# fhd-gs.net
KiCad netlist of a schematic drawn in Altium Designer
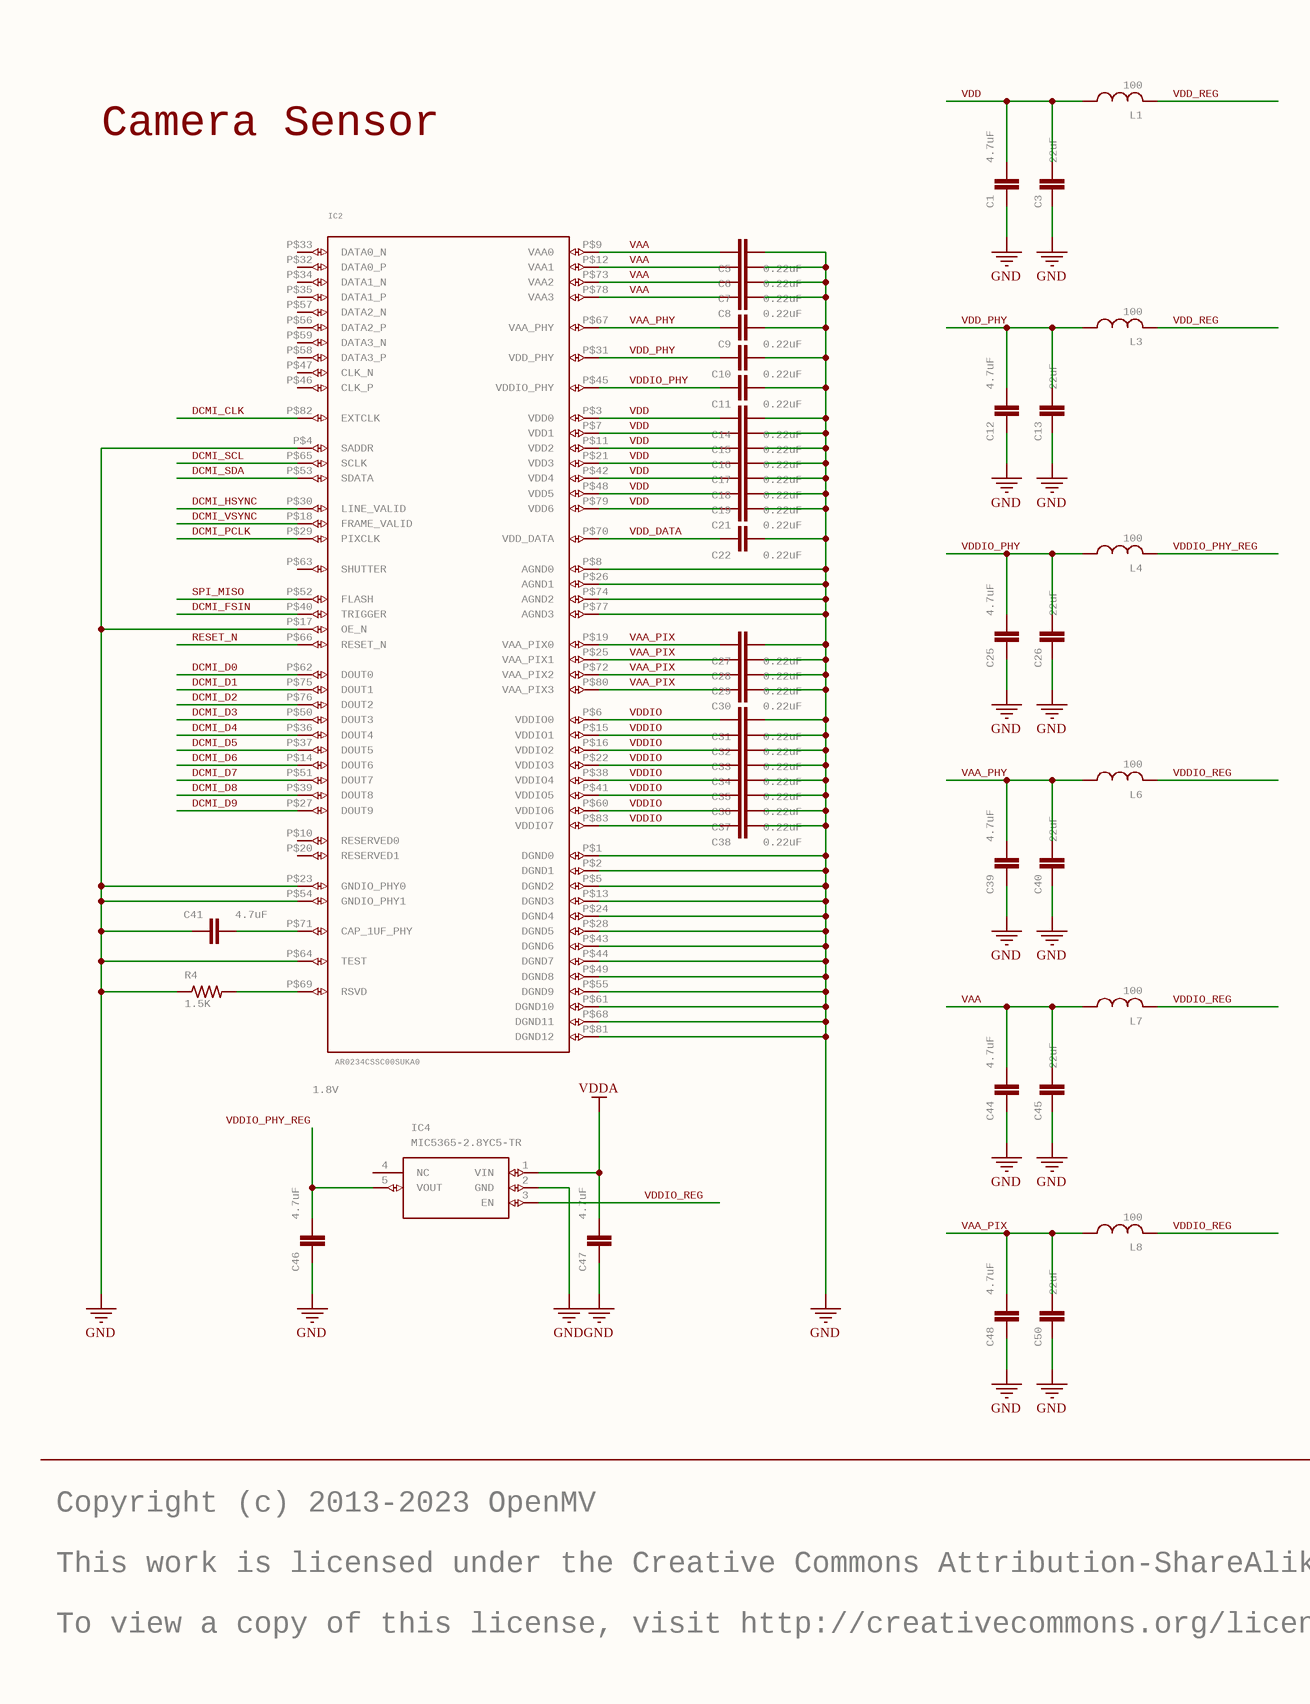
[diagram p0: fhd-gs.SchDoc, left]
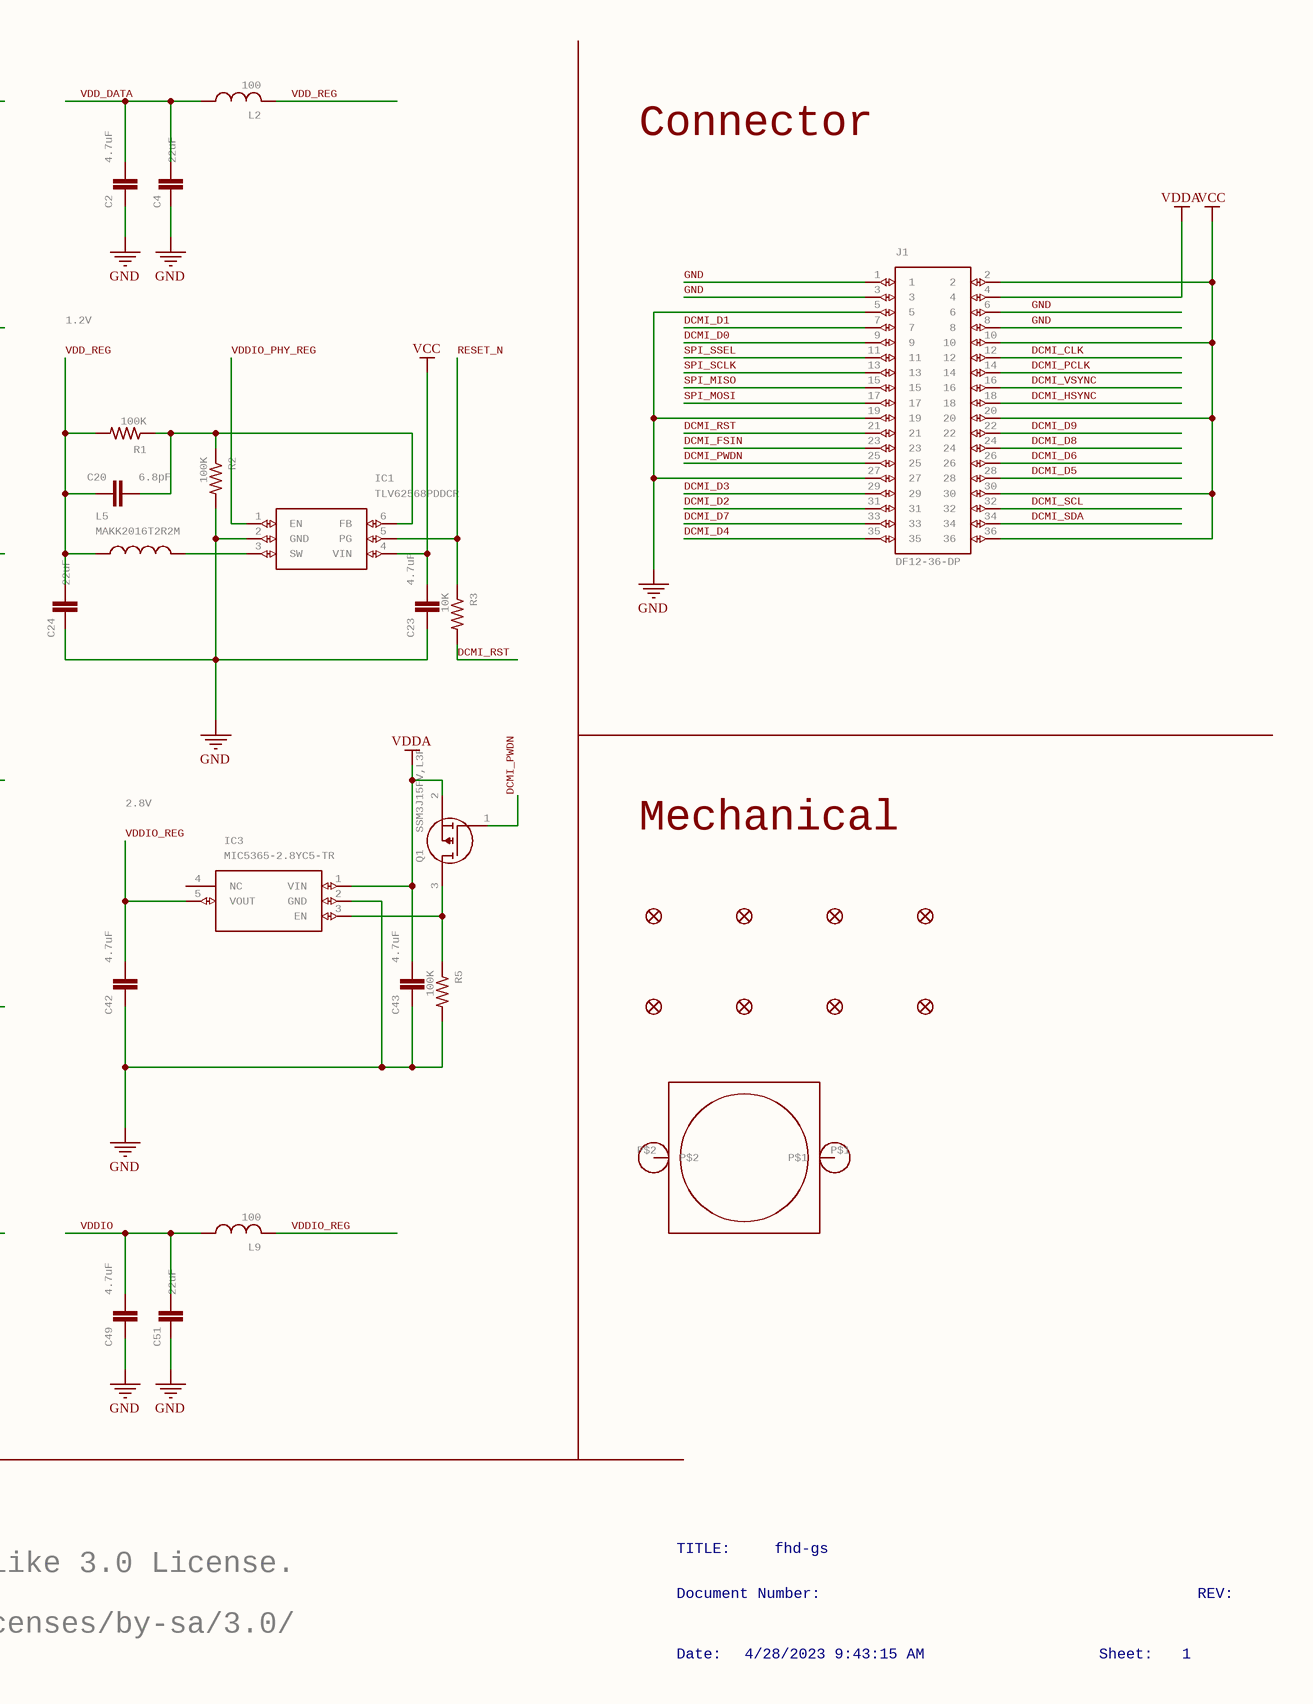
[diagram p1: fhd-gs.SchDoc, right]

(export (version "E")
  (design (tool "Eeschema 10.0.6"))
  (components
    (comp (ref "C1")
      (value "4.7uF")
      (footprint "0402")
      (description "0402 (1005 Metric) Nick Garner - TeleSense")
      (fields (field (name "MPN") "JMK105BBJ475MV-F"))
      (libsource (lib "") (part "CAP_0402_1"))
    )
    (comp (ref "C2")
      (value "4.7uF")
      (footprint "0402")
      (description "0402 (1005 Metric) Nick Garner - TeleSense")
      (fields (field (name "MPN") "JMK105BBJ475MV-F"))
      (libsource (lib "") (part "CAP_0402_1"))
    )
    (comp (ref "C3")
      (value "22uF")
      (footprint "0805")
      (fields (field (name "MPN") "CL21A226MQQNNNE"))
      (libsource (lib "camera-modules") (part "22UF-0805-6.3V-20%"))
    )
    (comp (ref "C4")
      (value "22uF")
      (footprint "0805")
      (fields (field (name "MPN") "CL21A226MQQNNNE"))
      (libsource (lib "camera-modules") (part "22UF-0805-6.3V-20%"))
    )
    (comp (ref "C5")
      (value "0.22uF")
      (footprint "C0201")
      (description "CAPACITOR, European symbol")
      (fields (field (name "MPN") "GRM033R60J224ME15D"))
      (libsource (lib "camera-modules") (part "C-EUC0201"))
    )
    (comp (ref "C6")
      (value "0.22uF")
      (footprint "C0201")
      (description "CAPACITOR, European symbol")
      (fields (field (name "MPN") "GRM033R60J224ME15D"))
      (libsource (lib "camera-modules") (part "C-EUC0201"))
    )
    (comp (ref "C7")
      (value "0.22uF")
      (footprint "C0201")
      (description "CAPACITOR, European symbol")
      (fields (field (name "MPN") "GRM033R60J224ME15D"))
      (libsource (lib "camera-modules") (part "C-EUC0201"))
    )
    (comp (ref "C8")
      (value "0.22uF")
      (footprint "C0201")
      (description "CAPACITOR, European symbol")
      (fields (field (name "MPN") "GRM033R60J224ME15D"))
      (libsource (lib "camera-modules") (part "C-EUC0201"))
    )
    (comp (ref "C9")
      (value "0.22uF")
      (footprint "C0201")
      (description "CAPACITOR, European symbol")
      (fields (field (name "MPN") "GRM033R60J224ME15D"))
      (libsource (lib "camera-modules") (part "C-EUC0201"))
    )
    (comp (ref "C10")
      (value "0.22uF")
      (footprint "C0201")
      (description "CAPACITOR, European symbol")
      (fields (field (name "MPN") "GRM033R60J224ME15D"))
      (libsource (lib "camera-modules") (part "C-EUC0201"))
    )
    (comp (ref "C11")
      (value "0.22uF")
      (footprint "C0201")
      (description "CAPACITOR, European symbol")
      (fields (field (name "MPN") "GRM033R60J224ME15D"))
      (libsource (lib "camera-modules") (part "C-EUC0201"))
    )
    (comp (ref "C12")
      (value "4.7uF")
      (footprint "0402")
      (description "0402 (1005 Metric) Nick Garner - TeleSense")
      (fields (field (name "MPN") "JMK105BBJ475MV-F"))
      (libsource (lib "") (part "CAP_0402_1"))
    )
    (comp (ref "C13")
      (value "22uF")
      (footprint "0805")
      (fields (field (name "MPN") "CL21A226MQQNNNE"))
      (libsource (lib "camera-modules") (part "22UF-0805-6.3V-20%"))
    )
    (comp (ref "C14")
      (value "0.22uF")
      (footprint "C0201")
      (description "CAPACITOR, European symbol")
      (fields (field (name "MPN") "GRM033R60J224ME15D"))
      (libsource (lib "camera-modules") (part "C-EUC0201"))
    )
    (comp (ref "C15")
      (value "0.22uF")
      (footprint "C0201")
      (description "CAPACITOR, European symbol")
      (fields (field (name "MPN") "GRM033R60J224ME15D"))
      (libsource (lib "camera-modules") (part "C-EUC0201"))
    )
    (comp (ref "C16")
      (value "0.22uF")
      (footprint "C0201")
      (description "CAPACITOR, European symbol")
      (fields (field (name "MPN") "GRM033R60J224ME15D"))
      (libsource (lib "camera-modules") (part "C-EUC0201"))
    )
    (comp (ref "C17")
      (value "0.22uF")
      (footprint "C0201")
      (description "CAPACITOR, European symbol")
      (fields (field (name "MPN") "GRM033R60J224ME15D"))
      (libsource (lib "camera-modules") (part "C-EUC0201"))
    )
    (comp (ref "C18")
      (value "0.22uF")
      (footprint "C0201")
      (description "CAPACITOR, European symbol")
      (fields (field (name "MPN") "GRM033R60J224ME15D"))
      (libsource (lib "camera-modules") (part "C-EUC0201"))
    )
    (comp (ref "C19")
      (value "0.22uF")
      (footprint "C0201")
      (description "CAPACITOR, European symbol")
      (fields (field (name "MPN") "GRM033R60J224ME15D"))
      (libsource (lib "camera-modules") (part "C-EUC0201"))
    )
    (comp (ref "C20")
      (value "6.8pF")
      (footprint "0402")
      (description "0402 (1005 Metric) Nick Garner - TeleSense")
      (fields (field (name "MPN") "GRM1555C1H6R8DA01D"))
      (libsource (lib "camera-modules") (part "CAP_0402"))
    )
    (comp (ref "C21")
      (value "0.22uF")
      (footprint "C0201")
      (description "CAPACITOR, European symbol")
      (fields (field (name "MPN") "GRM033R60J224ME15D"))
      (libsource (lib "camera-modules") (part "C-EUC0201"))
    )
    (comp (ref "C22")
      (value "0.22uF")
      (footprint "C0201")
      (description "CAPACITOR, European symbol")
      (fields (field (name "MPN") "GRM033R60J224ME15D"))
      (libsource (lib "camera-modules") (part "C-EUC0201"))
    )
    (comp (ref "C23")
      (value "4.7uF")
      (footprint "0402")
      (description "0402 (1005 Metric) Nick Garner - TeleSense")
      (fields (field (name "MPN") "JMK105BBJ475MV-F"))
      (libsource (lib "") (part "CAP_0402_1"))
    )
    (comp (ref "C24")
      (value "22uF")
      (footprint "0805")
      (fields (field (name "MPN") "CL21A226MQQNNNE"))
      (libsource (lib "camera-modules") (part "22UF-0805-6.3V-20%"))
    )
    (comp (ref "C25")
      (value "4.7uF")
      (footprint "0402")
      (description "0402 (1005 Metric) Nick Garner - TeleSense")
      (fields (field (name "MPN") "JMK105BBJ475MV-F"))
      (libsource (lib "") (part "CAP_0402_1"))
    )
    (comp (ref "C26")
      (value "22uF")
      (footprint "0805")
      (fields (field (name "MPN") "CL21A226MQQNNNE"))
      (libsource (lib "camera-modules") (part "22UF-0805-6.3V-20%"))
    )
    (comp (ref "C27")
      (value "0.22uF")
      (footprint "C0201")
      (description "CAPACITOR, European symbol")
      (fields (field (name "MPN") "GRM033R60J224ME15D"))
      (libsource (lib "camera-modules") (part "C-EUC0201"))
    )
    (comp (ref "C28")
      (value "0.22uF")
      (footprint "C0201")
      (description "CAPACITOR, European symbol")
      (fields (field (name "MPN") "GRM033R60J224ME15D"))
      (libsource (lib "camera-modules") (part "C-EUC0201"))
    )
    (comp (ref "C29")
      (value "0.22uF")
      (footprint "C0201")
      (description "CAPACITOR, European symbol")
      (fields (field (name "MPN") "GRM033R60J224ME15D"))
      (libsource (lib "camera-modules") (part "C-EUC0201"))
    )
    (comp (ref "C30")
      (value "0.22uF")
      (footprint "C0201")
      (description "CAPACITOR, European symbol")
      (fields (field (name "MPN") "GRM033R60J224ME15D"))
      (libsource (lib "camera-modules") (part "C-EUC0201"))
    )
    (comp (ref "C31")
      (value "0.22uF")
      (footprint "C0201")
      (description "CAPACITOR, European symbol")
      (fields (field (name "MPN") "GRM033R60J224ME15D"))
      (libsource (lib "camera-modules") (part "C-EUC0201"))
    )
    (comp (ref "C32")
      (value "0.22uF")
      (footprint "C0201")
      (description "CAPACITOR, European symbol")
      (fields (field (name "MPN") "GRM033R60J224ME15D"))
      (libsource (lib "camera-modules") (part "C-EUC0201"))
    )
    (comp (ref "C33")
      (value "0.22uF")
      (footprint "C0201")
      (description "CAPACITOR, European symbol")
      (fields (field (name "MPN") "GRM033R60J224ME15D"))
      (libsource (lib "camera-modules") (part "C-EUC0201"))
    )
    (comp (ref "C34")
      (value "0.22uF")
      (footprint "C0201")
      (description "CAPACITOR, European symbol")
      (fields (field (name "MPN") "GRM033R60J224ME15D"))
      (libsource (lib "camera-modules") (part "C-EUC0201"))
    )
    (comp (ref "C35")
      (value "0.22uF")
      (footprint "C0201")
      (description "CAPACITOR, European symbol")
      (fields (field (name "MPN") "GRM033R60J224ME15D"))
      (libsource (lib "camera-modules") (part "C-EUC0201"))
    )
    (comp (ref "C36")
      (value "0.22uF")
      (footprint "C0201")
      (description "CAPACITOR, European symbol")
      (fields (field (name "MPN") "GRM033R60J224ME15D"))
      (libsource (lib "camera-modules") (part "C-EUC0201"))
    )
    (comp (ref "C37")
      (value "0.22uF")
      (footprint "C0201")
      (description "CAPACITOR, European symbol")
      (fields (field (name "MPN") "GRM033R60J224ME15D"))
      (libsource (lib "camera-modules") (part "C-EUC0201"))
    )
    (comp (ref "C38")
      (value "0.22uF")
      (footprint "C0201")
      (description "CAPACITOR, European symbol")
      (fields (field (name "MPN") "GRM033R60J224ME15D"))
      (libsource (lib "camera-modules") (part "C-EUC0201"))
    )
    (comp (ref "C39")
      (value "4.7uF")
      (footprint "0402")
      (description "0402 (1005 Metric) Nick Garner - TeleSense")
      (fields (field (name "MPN") "JMK105BBJ475MV-F"))
      (libsource (lib "") (part "CAP_0402_1"))
    )
    (comp (ref "C40")
      (value "22uF")
      (footprint "0805")
      (fields (field (name "MPN") "CL21A226MQQNNNE"))
      (libsource (lib "camera-modules") (part "22UF-0805-6.3V-20%"))
    )
    (comp (ref "C41")
      (value "4.7uF")
      (footprint "0402")
      (description "0402 (1005 Metric) Nick Garner - TeleSense")
      (fields (field (name "MPN") "JMK105BBJ475MV-F"))
      (libsource (lib "camera-modules") (part "CAP_0402"))
    )
    (comp (ref "C42")
      (value "4.7uF")
      (footprint "0402")
      (description "0402 (1005 Metric) Nick Garner - TeleSense")
      (fields (field (name "MPN") "JMK105BBJ475MV-F"))
      (libsource (lib "") (part "CAP_0402_1"))
    )
    (comp (ref "C43")
      (value "4.7uF")
      (footprint "0402")
      (description "0402 (1005 Metric) Nick Garner - TeleSense")
      (fields (field (name "MPN") "JMK105BBJ475MV-F"))
      (libsource (lib "") (part "CAP_0402_1"))
    )
    (comp (ref "C44")
      (value "4.7uF")
      (footprint "0402")
      (description "0402 (1005 Metric) Nick Garner - TeleSense")
      (fields (field (name "MPN") "JMK105BBJ475MV-F"))
      (libsource (lib "") (part "CAP_0402_1"))
    )
    (comp (ref "C45")
      (value "22uF")
      (footprint "0805")
      (fields (field (name "MPN") "CL21A226MQQNNNE"))
      (libsource (lib "camera-modules") (part "22UF-0805-6.3V-20%"))
    )
    (comp (ref "C46")
      (value "4.7uF")
      (footprint "0402")
      (description "0402 (1005 Metric) Nick Garner - TeleSense")
      (fields (field (name "MPN") "JMK105BBJ475MV-F"))
      (libsource (lib "") (part "CAP_0402_1"))
    )
    (comp (ref "C47")
      (value "4.7uF")
      (footprint "0402")
      (description "0402 (1005 Metric) Nick Garner - TeleSense")
      (fields (field (name "MPN") "JMK105BBJ475MV-F"))
      (libsource (lib "") (part "CAP_0402_1"))
    )
    (comp (ref "C48")
      (value "4.7uF")
      (footprint "0402")
      (description "0402 (1005 Metric) Nick Garner - TeleSense")
      (fields (field (name "MPN") "JMK105BBJ475MV-F"))
      (libsource (lib "") (part "CAP_0402_1"))
    )
    (comp (ref "C49")
      (value "4.7uF")
      (footprint "0402")
      (description "0402 (1005 Metric) Nick Garner - TeleSense")
      (fields (field (name "MPN") "JMK105BBJ475MV-F"))
      (libsource (lib "") (part "CAP_0402_1"))
    )
    (comp (ref "C50")
      (value "22uF")
      (footprint "0805")
      (fields (field (name "MPN") "CL21A226MQQNNNE"))
      (libsource (lib "camera-modules") (part "22UF-0805-6.3V-20%"))
    )
    (comp (ref "C51")
      (value "22uF")
      (footprint "0805")
      (fields (field (name "MPN") "CL21A226MQQNNNE"))
      (libsource (lib "camera-modules") (part "22UF-0805-6.3V-20%"))
    )
    (comp (ref "FD1")
      (value "FIDUCIAL1X2")
      (footprint "FIDUCIAL-1X2")
      (fields (field (name "LIBRARYNAME") "SparkFun-Aesthetics"))
      (libsource (lib "camera-modules") (part "FIDUCIAL1X2"))
    )
    (comp (ref "FD2")
      (value "FIDUCIAL1X2")
      (footprint "FIDUCIAL-1X2")
      (fields (field (name "LIBRARYNAME") "SparkFun-Aesthetics"))
      (libsource (lib "camera-modules") (part "FIDUCIAL1X2"))
    )
    (comp (ref "FD3")
      (value "FIDUCIAL1X2")
      (footprint "FIDUCIAL-1X2")
      (fields (field (name "LIBRARYNAME") "SparkFun-Aesthetics"))
      (libsource (lib "camera-modules") (part "FIDUCIAL1X2"))
    )
    (comp (ref "FD4")
      (value "FIDUCIAL1X2")
      (footprint "FIDUCIAL-1X2")
      (fields (field (name "LIBRARYNAME") "SparkFun-Aesthetics"))
      (libsource (lib "camera-modules") (part "FIDUCIAL1X2"))
    )
    (comp (ref "FD5")
      (value "FIDUCIAL1X2")
      (footprint "FIDUCIAL-1X2")
      (fields (field (name "LIBRARYNAME") "SparkFun-Aesthetics"))
      (libsource (lib "camera-modules") (part "FIDUCIAL1X2"))
    )
    (comp (ref "FD6")
      (value "FIDUCIAL1X2")
      (footprint "FIDUCIAL-1X2")
      (fields (field (name "LIBRARYNAME") "SparkFun-Aesthetics"))
      (libsource (lib "camera-modules") (part "FIDUCIAL1X2"))
    )
    (comp (ref "FD7")
      (value "FIDUCIAL1X2")
      (footprint "FIDUCIAL-1X2")
      (fields (field (name "LIBRARYNAME") "SparkFun-Aesthetics"))
      (libsource (lib "camera-modules") (part "FIDUCIAL1X2"))
    )
    (comp (ref "FD8")
      (value "FIDUCIAL1X2")
      (footprint "FIDUCIAL-1X2")
      (fields (field (name "LIBRARYNAME") "SparkFun-Aesthetics"))
      (libsource (lib "camera-modules") (part "FIDUCIAL1X2"))
    )
    (comp (ref "H1")
      (value "LENSMOUNT20MM")
      (footprint "LENSMOUNT-20MM")
      (libsource (lib "camera-modules") (part "LENSMOUNT20MM"))
    )
    (comp (ref "IC1")
      (value "TLV62568PDDCR")
      (footprint "SOT95P280X110-6N")
      (fields (field (name "MOUSER_PART_NUMBER") "595-TLV62568PDDCR"))
      (libsource (lib "camera-modules") (part "TLV62568PDDCR"))
    )
    (comp (ref "IC2")
      (value "AR0234CSSC00SUKA0")
      (footprint "AR0234CSSC00SUKA0")
      (libsource (lib "camera-modules") (part "AR0234CSSC00SUKA0"))
    )
    (comp (ref "IC3")
      (value "MIC5365-2.8YC5-TR")
      (footprint "SOT65P210X110-5N")
      (description "IC REG LINEAR 2.8V 150MA SC70-5   Source:  Datasheet")
      (fields (field (name "MOUSER_PART_NUMBER") "998-MIC5365-2.8YC5TR"))
      (libsource (lib "camera-modules") (part "MIC5365-2.8YC5-TR"))
    )
    (comp (ref "IC4")
      (value "MIC5365-2.8YC5-TR")
      (footprint "SOT65P210X110-5N")
      (description "IC REG LINEAR 2.8V 150MA SC70-5   Source:  Datasheet")
      (fields (field (name "MOUSER_PART_NUMBER") "998-MIC5365-2.8YC5TR"))
      (libsource (lib "camera-modules") (part "MIC5365-2.8YC5-TR"))
    )
    (comp (ref "J1")
      (value "DF12-36-DP")
      (footprint "DF12-36-DP")
      (fields (field (name "MPN") "DF12NB(3.0)-36DP-0.5V(51)"))
      (libsource (lib "camera-modules") (part "DF12-36-DP"))
    )
    (comp (ref "L1")
      (value "100")
      (footprint "0402")
      (fields (field (name "MPN") "MFBM1V1005-101-R"))
      (libsource (lib "camera-modules") (part "INDUCTOR_0402"))
    )
    (comp (ref "L2")
      (value "100")
      (footprint "0402")
      (fields (field (name "MPN") "MFBM1V1005-101-R"))
      (libsource (lib "camera-modules") (part "INDUCTOR_0402"))
    )
    (comp (ref "L3")
      (value "100")
      (footprint "0402")
      (fields (field (name "MPN") "MFBM1V1005-101-R"))
      (libsource (lib "camera-modules") (part "INDUCTOR_0402"))
    )
    (comp (ref "L4")
      (value "100")
      (footprint "0402")
      (fields (field (name "MPN") "MFBM1V1005-101-R"))
      (libsource (lib "camera-modules") (part "INDUCTOR_0402"))
    )
    (comp (ref "L5")
      (value "MAKK2016T2R2M")
      (footprint "INDC2016X100N")
      (description "INDUCTOR, METAL CORE Check availability")
      (fields (field (name "MF") "Taiyo Yuden"))
      (libsource (lib "camera-modules") (part "MAKK2016T2R2M"))
    )
    (comp (ref "L6")
      (value "100")
      (footprint "0402")
      (fields (field (name "MPN") "MFBM1V1005-101-R"))
      (libsource (lib "camera-modules") (part "INDUCTOR_0402"))
    )
    (comp (ref "L7")
      (value "100")
      (footprint "0402")
      (fields (field (name "MPN") "MFBM1V1005-101-R"))
      (libsource (lib "camera-modules") (part "INDUCTOR_0402"))
    )
    (comp (ref "L8")
      (value "100")
      (footprint "0402")
      (fields (field (name "MPN") "MFBM1V1005-101-R"))
      (libsource (lib "camera-modules") (part "INDUCTOR_0402"))
    )
    (comp (ref "L9")
      (value "100")
      (footprint "0402")
      (fields (field (name "MPN") "MFBM1V1005-101-R"))
      (libsource (lib "camera-modules") (part "INDUCTOR_0402"))
    )
    (comp (ref "Q1")
      (value "SSM3J15FV,L3F")
      (footprint "SSM3J15FV")
      (description "MOSFET 30 V, P-channel Trench MOSFET   Source:  Datasheet")
      (libsource (lib "camera-modules") (part "PMXB120EPEZ"))
    )
    (comp (ref "R1")
      (value "100K")
      (footprint "R0402")
      (description "RESISTOR, American symbol")
      (fields (field (name "MPN") "AC0402FR-07100KL"))
      (libsource (lib "camera-modules") (part "R-US_R0402"))
    )
    (comp (ref "R2")
      (value "100K")
      (footprint "R0402")
      (description "RESISTOR, American symbol")
      (fields (field (name "MPN") "AC0402FR-07100KL"))
      (libsource (lib "camera-modules") (part "R-US_R0402"))
    )
    (comp (ref "R3")
      (value "10K")
      (footprint "R0402")
      (description "RESISTOR, American symbol")
      (fields (field (name "MPN") "AC0402FR-1310KL"))
      (libsource (lib "camera-modules") (part "R-US_R0402"))
    )
    (comp (ref "R4")
      (value "1.5K")
      (footprint "R0402")
      (description "RESISTOR, American symbol")
      (fields (field (name "MPN") "RC0402FR-131K5L"))
      (libsource (lib "camera-modules") (part "R-US_R0402"))
    )
    (comp (ref "R5")
      (value "100K")
      (footprint "R0402")
      (description "RESISTOR, American symbol")
      (fields (field (name "MPN") "AC0402FR-07100KL"))
      (libsource (lib "camera-modules") (part "R-US_R0402"))
    )
  )
  (nets
    (net (code "1") (name "/DCMI_CLK") (class "Default")
      (node (ref "IC2") (pin "P$82") (pinfunction "EXTCLK_P$82") (pintype "bidirectional"))
      (node (ref "J1") (pin "12") (pinfunction "12_12") (pintype "bidirectional"))
    )
    (net (code "2") (name "/DCMI_D0") (class "Default")
      (node (ref "IC2") (pin "P$62") (pinfunction "DOUT0_P$62") (pintype "bidirectional"))
      (node (ref "J1") (pin "9") (pinfunction "9_9") (pintype "bidirectional"))
    )
    (net (code "3") (name "/DCMI_D1") (class "Default")
      (node (ref "IC2") (pin "P$75") (pinfunction "DOUT1_P$75") (pintype "bidirectional"))
      (node (ref "J1") (pin "7") (pinfunction "7_7") (pintype "bidirectional"))
    )
    (net (code "4") (name "/DCMI_D2") (class "Default")
      (node (ref "IC2") (pin "P$76") (pinfunction "DOUT2_P$76") (pintype "bidirectional"))
      (node (ref "J1") (pin "31") (pinfunction "31_31") (pintype "bidirectional"))
    )
    (net (code "5") (name "/DCMI_D3") (class "Default")
      (node (ref "IC2") (pin "P$50") (pinfunction "DOUT3_P$50") (pintype "bidirectional"))
      (node (ref "J1") (pin "29") (pinfunction "29_29") (pintype "bidirectional"))
    )
    (net (code "6") (name "/DCMI_D4") (class "Default")
      (node (ref "IC2") (pin "P$36") (pinfunction "DOUT4_P$36") (pintype "bidirectional"))
      (node (ref "J1") (pin "35") (pinfunction "35_35") (pintype "bidirectional"))
    )
    (net (code "7") (name "/DCMI_D5") (class "Default")
      (node (ref "IC2") (pin "P$37") (pinfunction "DOUT5_P$37") (pintype "bidirectional"))
      (node (ref "J1") (pin "28") (pinfunction "28_28") (pintype "bidirectional"))
    )
    (net (code "8") (name "/DCMI_D6") (class "Default")
      (node (ref "IC2") (pin "P$14") (pinfunction "DOUT6_P$14") (pintype "bidirectional"))
      (node (ref "J1") (pin "26") (pinfunction "26_26") (pintype "bidirectional"))
    )
    (net (code "9") (name "/DCMI_D7") (class "Default")
      (node (ref "IC2") (pin "P$51") (pinfunction "DOUT7_P$51") (pintype "bidirectional"))
      (node (ref "J1") (pin "33") (pinfunction "33_33") (pintype "bidirectional"))
    )
    (net (code "10") (name "/DCMI_D8") (class "Default")
      (node (ref "IC2") (pin "P$39") (pinfunction "DOUT8_P$39") (pintype "bidirectional"))
      (node (ref "J1") (pin "24") (pinfunction "24_24") (pintype "bidirectional"))
    )
    (net (code "11") (name "/DCMI_D9") (class "Default")
      (node (ref "IC2") (pin "P$27") (pinfunction "DOUT9_P$27") (pintype "bidirectional"))
      (node (ref "J1") (pin "22") (pinfunction "22_22") (pintype "bidirectional"))
    )
    (net (code "12") (name "/DCMI_FSIN") (class "Default")
      (node (ref "IC2") (pin "P$40") (pinfunction "TRIGGER_P$40") (pintype "bidirectional"))
      (node (ref "J1") (pin "23") (pinfunction "23_23") (pintype "bidirectional"))
    )
    (net (code "13") (name "/DCMI_HSYNC") (class "Default")
      (node (ref "IC2") (pin "P$30") (pinfunction "LINE_VALID_P$30") (pintype "bidirectional"))
      (node (ref "J1") (pin "18") (pinfunction "18_18") (pintype "bidirectional"))
    )
    (net (code "14") (name "/DCMI_PCLK") (class "Default")
      (node (ref "IC2") (pin "P$29") (pinfunction "PIXCLK_P$29") (pintype "bidirectional"))
      (node (ref "J1") (pin "14") (pinfunction "14_14") (pintype "bidirectional"))
    )
    (net (code "15") (name "/DCMI_PWDN") (class "Default")
      (node (ref "J1") (pin "25") (pinfunction "25_25") (pintype "bidirectional"))
      (node (ref "Q1") (pin "1") (pinfunction "G_1") (pintype "bidirectional"))
    )
    (net (code "16") (name "/DCMI_RST") (class "Default")
      (node (ref "J1") (pin "21") (pinfunction "21_21") (pintype "bidirectional"))
      (node (ref "R3") (pin "2") (pinfunction "2_2") (pintype "passive"))
    )
    (net (code "17") (name "/DCMI_SCL") (class "Default")
      (node (ref "IC2") (pin "P$65") (pinfunction "SCLK_P$65") (pintype "bidirectional"))
      (node (ref "J1") (pin "32") (pinfunction "32_32") (pintype "bidirectional"))
    )
    (net (code "18") (name "/DCMI_SDA") (class "Default")
      (node (ref "IC2") (pin "P$53") (pinfunction "SDATA_P$53") (pintype "bidirectional"))
      (node (ref "J1") (pin "34") (pinfunction "34_34") (pintype "bidirectional"))
    )
    (net (code "19") (name "/DCMI_VSYNC") (class "Default")
      (node (ref "IC2") (pin "P$18") (pinfunction "FRAME_VALID_P$18") (pintype "bidirectional"))
      (node (ref "J1") (pin "16") (pinfunction "16_16") (pintype "bidirectional"))
    )
    (net (code "20") (name "/RESET_N") (class "Default")
      (node (ref "IC1") (pin "5") (pinfunction "PG_5") (pintype "bidirectional"))
      (node (ref "IC2") (pin "P$66") (pinfunction "RESET_N_P$66") (pintype "bidirectional"))
      (node (ref "R3") (pin "1") (pinfunction "1_1") (pintype "passive"))
    )
    (net (code "21") (name "/SPI_MISO") (class "Default")
      (node (ref "IC2") (pin "P$52") (pinfunction "FLASH_P$52") (pintype "bidirectional"))
      (node (ref "J1") (pin "15") (pinfunction "15_15") (pintype "bidirectional"))
    )
    (net (code "22") (name "/SPI_MOSI") (class "Default")
      (node (ref "J1") (pin "17") (pinfunction "17_17") (pintype "bidirectional"))
    )
    (net (code "23") (name "/SPI_SCLK") (class "Default")
      (node (ref "J1") (pin "13") (pinfunction "13_13") (pintype "bidirectional"))
    )
    (net (code "24") (name "/SPI_SSEL") (class "Default")
      (node (ref "J1") (pin "11") (pinfunction "11_11") (pintype "bidirectional"))
    )
    (net (code "25") (name "/VAA") (class "Default")
      (node (ref "C44") (pin "2") (pinfunction "2_2") (pintype "passive"))
      (node (ref "C45") (pin "2") (pinfunction "2_2") (pintype "passive"))
      (node (ref "C5") (pin "1") (pinfunction "1_1") (pintype "passive"))
      (node (ref "C6") (pin "1") (pinfunction "1_1") (pintype "passive"))
      (node (ref "C7") (pin "1") (pinfunction "1_1") (pintype "passive"))
      (node (ref "C8") (pin "1") (pinfunction "1_1") (pintype "passive"))
      (node (ref "IC2") (pin "P$12") (pinfunction "VAA1_P$12") (pintype "bidirectional"))
      (node (ref "IC2") (pin "P$73") (pinfunction "VAA2_P$73") (pintype "bidirectional"))
      (node (ref "IC2") (pin "P$78") (pinfunction "VAA3_P$78") (pintype "bidirectional"))
      (node (ref "IC2") (pin "P$9") (pinfunction "VAA0_P$9") (pintype "bidirectional"))
      (node (ref "L7") (pin "1") (pinfunction "P$1_1") (pintype "passive"))
    )
    (net (code "26") (name "/VAA_PHY") (class "Default")
      (node (ref "C39") (pin "2") (pinfunction "2_2") (pintype "passive"))
      (node (ref "C40") (pin "2") (pinfunction "2_2") (pintype "passive"))
      (node (ref "C9") (pin "1") (pinfunction "1_1") (pintype "passive"))
      (node (ref "IC2") (pin "P$67") (pinfunction "VAA_PHY_P$67") (pintype "bidirectional"))
      (node (ref "L6") (pin "1") (pinfunction "P$1_1") (pintype "passive"))
    )
    (net (code "27") (name "/VAA_PIX") (class "Default")
      (node (ref "C27") (pin "1") (pinfunction "1_1") (pintype "passive"))
      (node (ref "C28") (pin "1") (pinfunction "1_1") (pintype "passive"))
      (node (ref "C29") (pin "1") (pinfunction "1_1") (pintype "passive"))
      (node (ref "C30") (pin "1") (pinfunction "1_1") (pintype "passive"))
      (node (ref "C48") (pin "2") (pinfunction "2_2") (pintype "passive"))
      (node (ref "C50") (pin "2") (pinfunction "2_2") (pintype "passive"))
      (node (ref "IC2") (pin "P$19") (pinfunction "VAA_PIX0_P$19") (pintype "bidirectional"))
      (node (ref "IC2") (pin "P$25") (pinfunction "VAA_PIX1_P$25") (pintype "bidirectional"))
      (node (ref "IC2") (pin "P$72") (pinfunction "VAA_PIX2_P$72") (pintype "bidirectional"))
      (node (ref "IC2") (pin "P$80") (pinfunction "VAA_PIX3_P$80") (pintype "bidirectional"))
      (node (ref "L8") (pin "1") (pinfunction "P$1_1") (pintype "passive"))
    )
    (net (code "28") (name "/VDD") (class "Default")
      (node (ref "C1") (pin "2") (pinfunction "2_2") (pintype "passive"))
      (node (ref "C14") (pin "1") (pinfunction "1_1") (pintype "passive"))
      (node (ref "C15") (pin "1") (pinfunction "1_1") (pintype "passive"))
      (node (ref "C16") (pin "1") (pinfunction "1_1") (pintype "passive"))
      (node (ref "C17") (pin "1") (pinfunction "1_1") (pintype "passive"))
      (node (ref "C18") (pin "1") (pinfunction "1_1") (pintype "passive"))
      (node (ref "C19") (pin "1") (pinfunction "1_1") (pintype "passive"))
      (node (ref "C21") (pin "1") (pinfunction "1_1") (pintype "passive"))
      (node (ref "C3") (pin "2") (pinfunction "2_2") (pintype "passive"))
      (node (ref "IC2") (pin "P$11") (pinfunction "VDD2_P$11") (pintype "bidirectional"))
      (node (ref "IC2") (pin "P$21") (pinfunction "VDD3_P$21") (pintype "bidirectional"))
      (node (ref "IC2") (pin "P$3") (pinfunction "VDD0_P$3") (pintype "bidirectional"))
      (node (ref "IC2") (pin "P$42") (pinfunction "VDD4_P$42") (pintype "bidirectional"))
      (node (ref "IC2") (pin "P$48") (pinfunction "VDD5_P$48") (pintype "bidirectional"))
      (node (ref "IC2") (pin "P$7") (pinfunction "VDD1_P$7") (pintype "bidirectional"))
      (node (ref "IC2") (pin "P$79") (pinfunction "VDD6_P$79") (pintype "bidirectional"))
      (node (ref "L1") (pin "1") (pinfunction "P$1_1") (pintype "passive"))
    )
    (net (code "29") (name "/VDDIO") (class "Default")
      (node (ref "C31") (pin "1") (pinfunction "1_1") (pintype "passive"))
      (node (ref "C32") (pin "1") (pinfunction "1_1") (pintype "passive"))
      (node (ref "C33") (pin "1") (pinfunction "1_1") (pintype "passive"))
      (node (ref "C34") (pin "1") (pinfunction "1_1") (pintype "passive"))
      (node (ref "C35") (pin "1") (pinfunction "1_1") (pintype "passive"))
      (node (ref "C36") (pin "1") (pinfunction "1_1") (pintype "passive"))
      (node (ref "C37") (pin "1") (pinfunction "1_1") (pintype "passive"))
      (node (ref "C38") (pin "1") (pinfunction "1_1") (pintype "passive"))
      (node (ref "C49") (pin "2") (pinfunction "2_2") (pintype "passive"))
      (node (ref "C51") (pin "2") (pinfunction "2_2") (pintype "passive"))
      (node (ref "IC2") (pin "P$15") (pinfunction "VDDIO1_P$15") (pintype "bidirectional"))
      (node (ref "IC2") (pin "P$16") (pinfunction "VDDIO2_P$16") (pintype "bidirectional"))
      (node (ref "IC2") (pin "P$22") (pinfunction "VDDIO3_P$22") (pintype "bidirectional"))
      (node (ref "IC2") (pin "P$38") (pinfunction "VDDIO4_P$38") (pintype "bidirectional"))
      (node (ref "IC2") (pin "P$41") (pinfunction "VDDIO5_P$41") (pintype "bidirectional"))
      (node (ref "IC2") (pin "P$6") (pinfunction "VDDIO0_P$6") (pintype "bidirectional"))
      (node (ref "IC2") (pin "P$60") (pinfunction "VDDIO6_P$60") (pintype "bidirectional"))
      (node (ref "IC2") (pin "P$83") (pinfunction "VDDIO7_P$83") (pintype "bidirectional"))
      (node (ref "L9") (pin "1") (pinfunction "P$1_1") (pintype "passive"))
    )
    (net (code "30") (name "/VDDIO_PHY") (class "Default")
      (node (ref "C11") (pin "1") (pinfunction "1_1") (pintype "passive"))
      (node (ref "C25") (pin "2") (pinfunction "2_2") (pintype "passive"))
      (node (ref "C26") (pin "2") (pinfunction "2_2") (pintype "passive"))
      (node (ref "IC2") (pin "P$45") (pinfunction "VDDIO_PHY_P$45") (pintype "bidirectional"))
      (node (ref "L4") (pin "1") (pinfunction "P$1_1") (pintype "passive"))
    )
    (net (code "31") (name "/VDDIO_PHY_REG") (class "Default")
      (node (ref "C46") (pin "2") (pinfunction "2_2") (pintype "passive"))
      (node (ref "IC1") (pin "1") (pinfunction "EN_1") (pintype "bidirectional"))
      (node (ref "IC4") (pin "5") (pinfunction "VOUT_5") (pintype "bidirectional"))
      (node (ref "L4") (pin "2") (pinfunction "P$2_2") (pintype "passive"))
    )
    (net (code "32") (name "/VDDIO_REG") (class "Default")
      (node (ref "C42") (pin "2") (pinfunction "2_2") (pintype "passive"))
      (node (ref "IC3") (pin "5") (pinfunction "VOUT_5") (pintype "bidirectional"))
      (node (ref "IC4") (pin "3") (pinfunction "EN_3") (pintype "bidirectional"))
      (node (ref "L6") (pin "2") (pinfunction "P$2_2") (pintype "passive"))
      (node (ref "L7") (pin "2") (pinfunction "P$2_2") (pintype "passive"))
      (node (ref "L8") (pin "2") (pinfunction "P$2_2") (pintype "passive"))
      (node (ref "L9") (pin "2") (pinfunction "P$2_2") (pintype "passive"))
    )
    (net (code "33") (name "/VDD_DATA") (class "Default")
      (node (ref "C2") (pin "2") (pinfunction "2_2") (pintype "passive"))
      (node (ref "C22") (pin "1") (pinfunction "1_1") (pintype "passive"))
      (node (ref "C4") (pin "2") (pinfunction "2_2") (pintype "passive"))
      (node (ref "IC2") (pin "P$70") (pinfunction "VDD_DATA_P$70") (pintype "bidirectional"))
      (node (ref "L2") (pin "1") (pinfunction "P$1_1") (pintype "passive"))
    )
    (net (code "34") (name "/VDD_PHY") (class "Default")
      (node (ref "C10") (pin "1") (pinfunction "1_1") (pintype "passive"))
      (node (ref "C12") (pin "2") (pinfunction "2_2") (pintype "passive"))
      (node (ref "C13") (pin "2") (pinfunction "2_2") (pintype "passive"))
      (node (ref "IC2") (pin "P$31") (pinfunction "VDD_PHY_P$31") (pintype "bidirectional"))
      (node (ref "L3") (pin "1") (pinfunction "P$1_1") (pintype "passive"))
    )
    (net (code "35") (name "/VDD_REG") (class "Default")
      (node (ref "C20") (pin "1") (pinfunction "1_1") (pintype "passive"))
      (node (ref "C24") (pin "2") (pinfunction "2_2") (pintype "passive"))
      (node (ref "L1") (pin "2") (pinfunction "P$2_2") (pintype "passive"))
      (node (ref "L2") (pin "2") (pinfunction "P$2_2") (pintype "passive"))
      (node (ref "L3") (pin "2") (pinfunction "P$2_2") (pintype "passive"))
      (node (ref "L5") (pin "1") (pinfunction "1_1") (pintype "passive"))
      (node (ref "R1") (pin "2") (pinfunction "2_2") (pintype "passive"))
    )
    (net (code "36") (name "GND") (class "Default")
      (node (ref "C1") (pin "1") (pinfunction "1_1") (pintype "passive"))
      (node (ref "C10") (pin "2") (pinfunction "2_2") (pintype "passive"))
      (node (ref "C11") (pin "2") (pinfunction "2_2") (pintype "passive"))
      (node (ref "C12") (pin "1") (pinfunction "1_1") (pintype "passive"))
      (node (ref "C13") (pin "1") (pinfunction "1_1") (pintype "passive"))
      (node (ref "C14") (pin "2") (pinfunction "2_2") (pintype "passive"))
      (node (ref "C15") (pin "2") (pinfunction "2_2") (pintype "passive"))
      (node (ref "C16") (pin "2") (pinfunction "2_2") (pintype "passive"))
      (node (ref "C17") (pin "2") (pinfunction "2_2") (pintype "passive"))
      (node (ref "C18") (pin "2") (pinfunction "2_2") (pintype "passive"))
      (node (ref "C19") (pin "2") (pinfunction "2_2") (pintype "passive"))
      (node (ref "C2") (pin "1") (pinfunction "1_1") (pintype "passive"))
      (node (ref "C21") (pin "2") (pinfunction "2_2") (pintype "passive"))
      (node (ref "C22") (pin "2") (pinfunction "2_2") (pintype "passive"))
      (node (ref "C23") (pin "1") (pinfunction "1_1") (pintype "passive"))
      (node (ref "C24") (pin "1") (pinfunction "1_1") (pintype "passive"))
      (node (ref "C25") (pin "1") (pinfunction "1_1") (pintype "passive"))
      (node (ref "C26") (pin "1") (pinfunction "1_1") (pintype "passive"))
      (node (ref "C27") (pin "2") (pinfunction "2_2") (pintype "passive"))
      (node (ref "C28") (pin "2") (pinfunction "2_2") (pintype "passive"))
      (node (ref "C29") (pin "2") (pinfunction "2_2") (pintype "passive"))
      (node (ref "C3") (pin "1") (pinfunction "1_1") (pintype "passive"))
      (node (ref "C30") (pin "2") (pinfunction "2_2") (pintype "passive"))
      (node (ref "C31") (pin "2") (pinfunction "2_2") (pintype "passive"))
      (node (ref "C32") (pin "2") (pinfunction "2_2") (pintype "passive"))
      (node (ref "C33") (pin "2") (pinfunction "2_2") (pintype "passive"))
      (node (ref "C34") (pin "2") (pinfunction "2_2") (pintype "passive"))
      (node (ref "C35") (pin "2") (pinfunction "2_2") (pintype "passive"))
      (node (ref "C36") (pin "2") (pinfunction "2_2") (pintype "passive"))
      (node (ref "C37") (pin "2") (pinfunction "2_2") (pintype "passive"))
      (node (ref "C38") (pin "2") (pinfunction "2_2") (pintype "passive"))
      (node (ref "C39") (pin "1") (pinfunction "1_1") (pintype "passive"))
      (node (ref "C4") (pin "1") (pinfunction "1_1") (pintype "passive"))
      (node (ref "C40") (pin "1") (pinfunction "1_1") (pintype "passive"))
      (node (ref "C41") (pin "1") (pinfunction "1_1") (pintype "passive"))
      (node (ref "C42") (pin "1") (pinfunction "1_1") (pintype "passive"))
      (node (ref "C43") (pin "1") (pinfunction "1_1") (pintype "passive"))
      (node (ref "C44") (pin "1") (pinfunction "1_1") (pintype "passive"))
      (node (ref "C45") (pin "1") (pinfunction "1_1") (pintype "passive"))
      (node (ref "C46") (pin "1") (pinfunction "1_1") (pintype "passive"))
      (node (ref "C47") (pin "1") (pinfunction "1_1") (pintype "passive"))
      (node (ref "C48") (pin "1") (pinfunction "1_1") (pintype "passive"))
      (node (ref "C49") (pin "1") (pinfunction "1_1") (pintype "passive"))
      (node (ref "C5") (pin "2") (pinfunction "2_2") (pintype "passive"))
      (node (ref "C50") (pin "1") (pinfunction "1_1") (pintype "passive"))
      (node (ref "C51") (pin "1") (pinfunction "1_1") (pintype "passive"))
      (node (ref "C6") (pin "2") (pinfunction "2_2") (pintype "passive"))
      (node (ref "C7") (pin "2") (pinfunction "2_2") (pintype "passive"))
      (node (ref "C8") (pin "2") (pinfunction "2_2") (pintype "passive"))
      (node (ref "C9") (pin "2") (pinfunction "2_2") (pintype "passive"))
      (node (ref "IC1") (pin "2") (pinfunction "GND_2") (pintype "bidirectional"))
      (node (ref "IC2") (pin "P$1") (pinfunction "DGND0_P$1") (pintype "bidirectional"))
      (node (ref "IC2") (pin "P$13") (pinfunction "DGND3_P$13") (pintype "bidirectional"))
      (node (ref "IC2") (pin "P$17") (pinfunction "OE_N_P$17") (pintype "bidirectional"))
      (node (ref "IC2") (pin "P$2") (pinfunction "DGND1_P$2") (pintype "bidirectional"))
      (node (ref "IC2") (pin "P$23") (pinfunction "GNDIO_PHY0_P$23") (pintype "bidirectional"))
      (node (ref "IC2") (pin "P$24") (pinfunction "DGND4_P$24") (pintype "bidirectional"))
      (node (ref "IC2") (pin "P$26") (pinfunction "AGND1_P$26") (pintype "bidirectional"))
      (node (ref "IC2") (pin "P$28") (pinfunction "DGND5_P$28") (pintype "bidirectional"))
      (node (ref "IC2") (pin "P$4") (pinfunction "SADDR_P$4") (pintype "bidirectional"))
      (node (ref "IC2") (pin "P$43") (pinfunction "DGND6_P$43") (pintype "bidirectional"))
      (node (ref "IC2") (pin "P$44") (pinfunction "DGND7_P$44") (pintype "bidirectional"))
      (node (ref "IC2") (pin "P$49") (pinfunction "DGND8_P$49") (pintype "bidirectional"))
      (node (ref "IC2") (pin "P$5") (pinfunction "DGND2_P$5") (pintype "bidirectional"))
      (node (ref "IC2") (pin "P$54") (pinfunction "GNDIO_PHY1_P$54") (pintype "bidirectional"))
      (node (ref "IC2") (pin "P$55") (pinfunction "DGND9_P$55") (pintype "bidirectional"))
      (node (ref "IC2") (pin "P$61") (pinfunction "DGND10_P$61") (pintype "bidirectional"))
      (node (ref "IC2") (pin "P$64") (pinfunction "TEST_P$64") (pintype "bidirectional"))
      (node (ref "IC2") (pin "P$68") (pinfunction "DGND11_P$68") (pintype "bidirectional"))
      (node (ref "IC2") (pin "P$74") (pinfunction "AGND2_P$74") (pintype "bidirectional"))
      (node (ref "IC2") (pin "P$77") (pinfunction "AGND3_P$77") (pintype "bidirectional"))
      (node (ref "IC2") (pin "P$8") (pinfunction "AGND0_P$8") (pintype "bidirectional"))
      (node (ref "IC2") (pin "P$81") (pinfunction "DGND12_P$81") (pintype "bidirectional"))
      (node (ref "IC3") (pin "2") (pinfunction "GND_2") (pintype "bidirectional"))
      (node (ref "IC4") (pin "2") (pinfunction "GND_2") (pintype "bidirectional"))
      (node (ref "J1") (pin "1") (pinfunction "1_1") (pintype "bidirectional"))
      (node (ref "J1") (pin "19") (pinfunction "19_19") (pintype "bidirectional"))
      (node (ref "J1") (pin "27") (pinfunction "27_27") (pintype "bidirectional"))
      (node (ref "J1") (pin "3") (pinfunction "3_3") (pintype "bidirectional"))
      (node (ref "J1") (pin "5") (pinfunction "5_5") (pintype "bidirectional"))
      (node (ref "J1") (pin "6") (pinfunction "6_6") (pintype "bidirectional"))
      (node (ref "J1") (pin "8") (pinfunction "8_8") (pintype "bidirectional"))
      (node (ref "R2") (pin "2") (pinfunction "2_2") (pintype "passive"))
      (node (ref "R4") (pin "1") (pinfunction "1_1") (pintype "passive"))
      (node (ref "R5") (pin "2") (pinfunction "2_2") (pintype "passive"))
    )
    (net (code "37") (name "Net-(IC1-FB)") (class "Default")
      (node (ref "C20") (pin "2") (pinfunction "2_2") (pintype "passive"))
      (node (ref "IC1") (pin "6") (pinfunction "FB_6") (pintype "bidirectional"))
      (node (ref "R1") (pin "1") (pinfunction "1_1") (pintype "passive"))
      (node (ref "R2") (pin "1") (pinfunction "1_1") (pintype "passive"))
    )
    (net (code "38") (name "Net-(IC1-SW)") (class "Default")
      (node (ref "IC1") (pin "3") (pinfunction "SW_3") (pintype "bidirectional"))
      (node (ref "L5") (pin "2") (pinfunction "2_2") (pintype "passive"))
    )
    (net (code "39") (name "Net-(IC2-CAP_1UF_PHY)") (class "Default")
      (node (ref "C41") (pin "2") (pinfunction "2_2") (pintype "passive"))
      (node (ref "IC2") (pin "P$71") (pinfunction "CAP_1UF_PHY_P$71") (pintype "bidirectional"))
    )
    (net (code "40") (name "Net-(IC2-RSVD)") (class "Default")
      (node (ref "IC2") (pin "P$69") (pinfunction "RSVD_P$69") (pintype "bidirectional"))
      (node (ref "R4") (pin "2") (pinfunction "2_2") (pintype "passive"))
    )
    (net (code "41") (name "Net-(IC3-EN)") (class "Default")
      (node (ref "IC3") (pin "3") (pinfunction "EN_3") (pintype "bidirectional"))
      (node (ref "Q1") (pin "3") (pinfunction "D_3") (pintype "bidirectional"))
      (node (ref "R5") (pin "1") (pinfunction "1_1") (pintype "passive"))
    )
    (net (code "42") (name "VCC") (class "Default")
      (node (ref "C23") (pin "2") (pinfunction "2_2") (pintype "passive"))
      (node (ref "IC1") (pin "4") (pinfunction "VIN_4") (pintype "bidirectional"))
      (node (ref "J1") (pin "10") (pinfunction "10_10") (pintype "bidirectional"))
      (node (ref "J1") (pin "2") (pinfunction "2_2") (pintype "bidirectional"))
      (node (ref "J1") (pin "20") (pinfunction "20_20") (pintype "bidirectional"))
      (node (ref "J1") (pin "30") (pinfunction "30_30") (pintype "bidirectional"))
      (node (ref "J1") (pin "36") (pinfunction "36_36") (pintype "bidirectional"))
    )
    (net (code "43") (name "VDDA") (class "Default")
      (node (ref "C43") (pin "2") (pinfunction "2_2") (pintype "passive"))
      (node (ref "C47") (pin "2") (pinfunction "2_2") (pintype "passive"))
      (node (ref "IC3") (pin "1") (pinfunction "VIN_1") (pintype "bidirectional"))
      (node (ref "IC4") (pin "1") (pinfunction "VIN_1") (pintype "bidirectional"))
      (node (ref "J1") (pin "4") (pinfunction "4_4") (pintype "bidirectional"))
      (node (ref "Q1") (pin "2") (pinfunction "S_2") (pintype "bidirectional"))
    )
    (net (code "44") (name "unconnected-(H1-PadP$1)") (class "Default")
      (node (ref "H1") (pin "P$1") (pinfunction "P$1_P$1") (pintype "power_in"))
    )
    (net (code "45") (name "unconnected-(H1-PadP$2)") (class "Default")
      (node (ref "H1") (pin "P$2") (pinfunction "P$2_P$2") (pintype "power_in"))
    )
    (net (code "46") (name "unconnected-(IC2-CLK_N-PadP$47)") (class "Default")
      (node (ref "IC2") (pin "P$47") (pinfunction "CLK_N_P$47") (pintype "bidirectional"))
    )
    (net (code "47") (name "unconnected-(IC2-CLK_P-PadP$46)") (class "Default")
      (node (ref "IC2") (pin "P$46") (pinfunction "CLK_P_P$46") (pintype "bidirectional"))
    )
    (net (code "48") (name "unconnected-(IC2-DATA0_N-PadP$33)") (class "Default")
      (node (ref "IC2") (pin "P$33") (pinfunction "DATA0_N_P$33") (pintype "bidirectional"))
    )
    (net (code "49") (name "unconnected-(IC2-DATA0_P-PadP$32)") (class "Default")
      (node (ref "IC2") (pin "P$32") (pinfunction "DATA0_P_P$32") (pintype "bidirectional"))
    )
    (net (code "50") (name "unconnected-(IC2-DATA1_N-PadP$34)") (class "Default")
      (node (ref "IC2") (pin "P$34") (pinfunction "DATA1_N_P$34") (pintype "bidirectional"))
    )
    (net (code "51") (name "unconnected-(IC2-DATA1_P-PadP$35)") (class "Default")
      (node (ref "IC2") (pin "P$35") (pinfunction "DATA1_P_P$35") (pintype "bidirectional"))
    )
    (net (code "52") (name "unconnected-(IC2-DATA2_N-PadP$57)") (class "Default")
      (node (ref "IC2") (pin "P$57") (pinfunction "DATA2_N_P$57") (pintype "bidirectional"))
    )
    (net (code "53") (name "unconnected-(IC2-DATA2_P-PadP$56)") (class "Default")
      (node (ref "IC2") (pin "P$56") (pinfunction "DATA2_P_P$56") (pintype "bidirectional"))
    )
    (net (code "54") (name "unconnected-(IC2-DATA3_N-PadP$59)") (class "Default")
      (node (ref "IC2") (pin "P$59") (pinfunction "DATA3_N_P$59") (pintype "bidirectional"))
    )
    (net (code "55") (name "unconnected-(IC2-DATA3_P-PadP$58)") (class "Default")
      (node (ref "IC2") (pin "P$58") (pinfunction "DATA3_P_P$58") (pintype "bidirectional"))
    )
    (net (code "56") (name "unconnected-(IC2-RESERVED0-PadP$10)") (class "Default")
      (node (ref "IC2") (pin "P$10") (pinfunction "RESERVED0_P$10") (pintype "bidirectional"))
    )
    (net (code "57") (name "unconnected-(IC2-RESERVED1-PadP$20)") (class "Default")
      (node (ref "IC2") (pin "P$20") (pinfunction "RESERVED1_P$20") (pintype "bidirectional"))
    )
    (net (code "58") (name "unconnected-(IC2-SHUTTER-PadP$63)") (class "Default")
      (node (ref "IC2") (pin "P$63") (pinfunction "SHUTTER_P$63") (pintype "bidirectional"))
    )
    (net (code "59") (name "unconnected-(IC3-NC-Pad4)") (class "Default")
      (node (ref "IC3") (pin "4") (pinfunction "NC_4") (pintype "passive"))
    )
    (net (code "60") (name "unconnected-(IC4-NC-Pad4)") (class "Default")
      (node (ref "IC4") (pin "4") (pinfunction "NC_4") (pintype "passive"))
    )
  )
)
